# design.net
KiCad netlist of a schematic drawn in Altium Designer
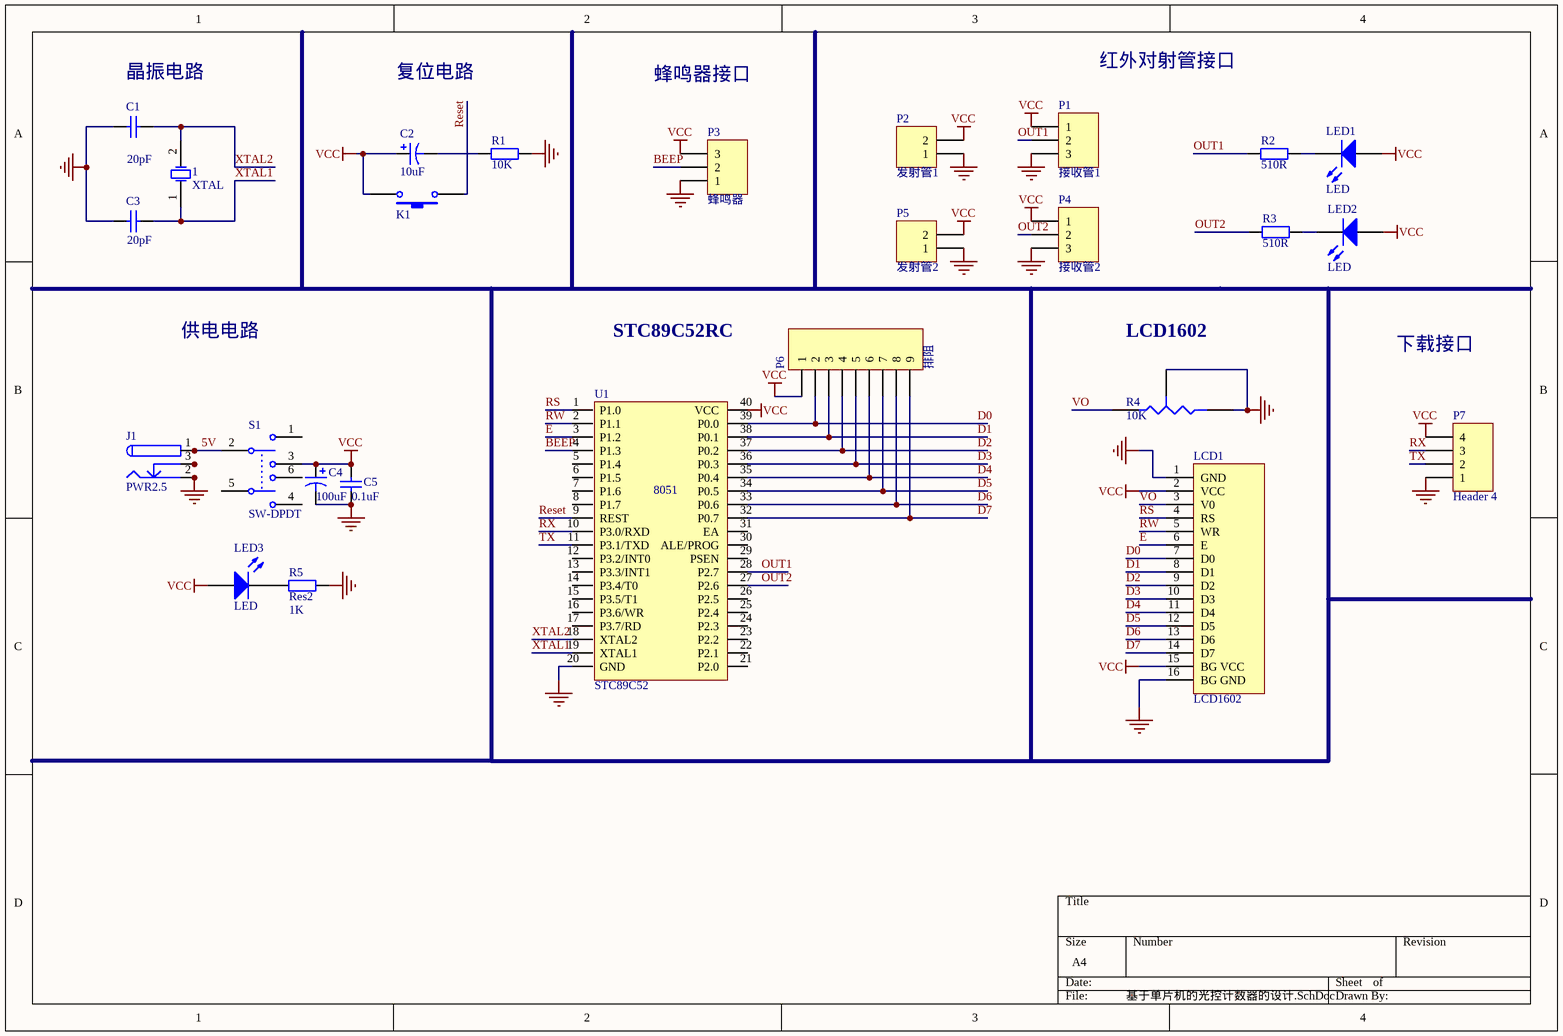
[diagram p0: 基于单片机的光控计数器的设计.SchDoc]

(export (version "E")
  (design (tool "Eeschema 10.0.6"))
  (components
    (comp (ref "1")
      (value "XTAL")
      (footprint "XTAL")
      (description "Crystal Oscillator")
      (fields (field (name "PUBLISHER") "Altium Limited"))
      (libsource (lib "Miscellaneous Devices") (part "XTAL"))
    )
    (comp (ref "C1")
      (value "20pF")
      (footprint "RAD-0.1")
      (description "Capacitor")
      (fields (field (name "Comment") "Cap") (field (name "PUBLISHER") "Altium Limited"))
      (libsource (lib "Miscellaneous Devices") (part "Cap"))
    )
    (comp (ref "C2")
      (value "10uF")
      (footprint "RB.1/.2")
      (description "Polarized Capacitor (Radial)")
      (fields (field (name "Comment") "Cap Pol1") (field (name "PUBLISHER") "Altium Limited"))
      (libsource (lib "Miscellaneous Devices") (part "Cap Pol1"))
    )
    (comp (ref "C3")
      (value "20pF")
      (footprint "RAD-0.1")
      (description "Capacitor")
      (fields (field (name "Comment") "Cap") (field (name "PUBLISHER") "Altium Limited"))
      (libsource (lib "Miscellaneous Devices") (part "Cap"))
    )
    (comp (ref "C4")
      (value "100uF")
      (footprint "RB.1/.2")
      (description "Polarized Capacitor (Radial)")
      (fields (field (name "Comment") "Cap Pol1") (field (name "PUBLISHER") "Altium Limited"))
      (libsource (lib "Miscellaneous Devices") (part "Cap Pol1"))
    )
    (comp (ref "C5")
      (value "0.1uF")
      (footprint "RAD-0.1")
      (description "Capacitor")
      (fields (field (name "Comment") "Cap") (field (name "PUBLISHER") "Altium Limited"))
      (libsource (lib "Miscellaneous Devices") (part "Cap"))
    )
    (comp (ref "J1")
      (value "PWR2.5")
      (footprint "KLD-0202")
      (description "Low Voltage Power Supply Connector")
      (fields (field (name "PUBLISHER") "Altium Limited"))
      (libsource (lib "Miscellaneous Connectors") (part "PWR2.5"))
    )
    (comp (ref "K1") (value "四脚按键") (footprint "四脚按键") (libsource (lib "My library") (part "四脚按键")))
    (comp (ref "LCD1")
      (value "LCD1602")
      (footprint "LCD1602")
      (libsource (lib "My library") (part "LCD1602"))
    )
    (comp (ref "LED1") (value "LED") (footprint "LED") (libsource (lib "My library") (part "LED")))
    (comp (ref "LED2") (value "LED") (footprint "LED") (libsource (lib "My library") (part "LED")))
    (comp (ref "LED3") (value "LED") (footprint "LED") (libsource (lib "My library") (part "LED")))
    (comp (ref "P1")
      (value "接收管1")
      (footprint "HDR1X3")
      (description "Header, 3-Pin")
      (fields (field (name "PUBLISHER") "Altium Limited"))
      (libsource (lib "") (part "Header 3_1"))
    )
    (comp (ref "P2")
      (value "发射管1")
      (footprint "HDR1X2")
      (description "Header, 2-Pin")
      (fields (field (name "PUBLISHER") "Altium Limited"))
      (libsource (lib "Miscellaneous Connectors") (part "Header 2"))
    )
    (comp (ref "P3")
      (value "蜂鸣器")
      (footprint "HDR1X3")
      (description "Header, 3-Pin")
      (fields (field (name "PUBLISHER") "Altium Limited"))
      (libsource (lib "Miscellaneous Connectors") (part "Header 3"))
    )
    (comp (ref "P4")
      (value "接收管2")
      (footprint "HDR1X3")
      (description "Header, 3-Pin")
      (fields (field (name "PUBLISHER") "Altium Limited"))
      (libsource (lib "") (part "Header 3_1"))
    )
    (comp (ref "P5")
      (value "发射管2")
      (footprint "HDR1X2")
      (description "Header, 2-Pin")
      (fields (field (name "PUBLISHER") "Altium Limited"))
      (libsource (lib "Miscellaneous Connectors") (part "Header 2"))
    )
    (comp (ref "P6")
      (value "排阻")
      (footprint "HDR1X9")
      (description "Header, 9-Pin")
      (fields (field (name "PUBLISHER") "Altium Limited"))
      (libsource (lib "Miscellaneous Connectors") (part "Header 9"))
    )
    (comp (ref "P7")
      (value "Header 4")
      (footprint "HDR1X4")
      (description "Header, 4-Pin")
      (fields (field (name "PUBLISHER") "Altium Limited"))
      (libsource (lib "Miscellaneous Connectors") (part "Header 4"))
    )
    (comp (ref "R1")
      (value "10K")
      (footprint "AXIAL-0.4")
      (description "Resistor")
      (fields (field (name "Comment") "Res2") (field (name "PUBLISHER") "Altium Limited"))
      (libsource (lib "Miscellaneous Devices") (part "Res2"))
    )
    (comp (ref "R2")
      (value "510R")
      (footprint "AXIAL-0.4")
      (description "Resistor")
      (fields (field (name "Comment") "Res2") (field (name "PUBLISHER") "Altium Limited"))
      (libsource (lib "") (part "Res2_1"))
    )
    (comp (ref "R3")
      (value "510R")
      (footprint "AXIAL-0.4")
      (description "Resistor")
      (fields (field (name "Comment") "Res2") (field (name "PUBLISHER") "Altium Limited"))
      (libsource (lib "") (part "Res2_1"))
    )
    (comp (ref "R4")
      (value "10K")
      (footprint "电位器")
      (description "Tapped Resistor")
      (fields (field (name "Comment") "Res Tap") (field (name "PUBLISHER") "Altium Limited"))
      (libsource (lib "Miscellaneous Devices") (part "Res Tap"))
    )
    (comp (ref "R5")
      (value "Res2")
      (footprint "AXIAL-0.4")
      (description "Resistor")
      (fields (field (name "ALTIUM_VALUE") "1K") (field (name "PUBLISHER") "Altium Limited"))
      (libsource (lib "") (part "Res2_1"))
    )
    (comp (ref "S1")
      (value "SW-DPDT")
      (footprint "SWITCH_B1")
      (description "单刀双掷开关")
      (fields (field (name "PUBLISHER") "Altium Limited"))
      (libsource (lib "Fszhang") (part "SW-DPDT"))
    )
    (comp (ref "U1") (value "STC89C52") (footprint "DIP-40") (libsource (lib "My library") (part "STC89C51")))
  )
  (nets
    (net (code "1") (name "/5V") (class "Default")
      (node (ref "J1") (pin "1") (pinfunction "1_1") (pintype "power_in"))
      (node (ref "J1") (pin "1A") (pinfunction "1A_1A") (pintype "power_in"))
      (node (ref "J1") (pin "1B") (pinfunction "1B_1B") (pintype "power_in"))
      (node (ref "S1") (pin "2") (pinfunction "2_2") (pintype "passive"))
    )
    (net (code "2") (name "/BEEP") (class "Default")
      (node (ref "P3") (pin "2") (pinfunction "2_2") (pintype "passive"))
      (node (ref "U1") (pin "4") (pinfunction "P1.3_4") (pintype "passive"))
    )
    (net (code "3") (name "/D0") (class "Default")
      (node (ref "LCD1") (pin "7") (pinfunction "D0_7") (pintype "power_in"))
      (node (ref "P6") (pin "2") (pinfunction "2_2") (pintype "passive"))
      (node (ref "U1") (pin "39") (pinfunction "P0.0_39") (pintype "passive"))
    )
    (net (code "4") (name "/D1") (class "Default")
      (node (ref "LCD1") (pin "8") (pinfunction "D1_8") (pintype "power_in"))
      (node (ref "P6") (pin "3") (pinfunction "3_3") (pintype "passive"))
      (node (ref "U1") (pin "38") (pinfunction "P0.1_38") (pintype "passive"))
    )
    (net (code "5") (name "/D2") (class "Default")
      (node (ref "LCD1") (pin "9") (pinfunction "D2_9") (pintype "power_in"))
      (node (ref "P6") (pin "4") (pinfunction "4_4") (pintype "passive"))
      (node (ref "U1") (pin "37") (pinfunction "P0.2_37") (pintype "passive"))
    )
    (net (code "6") (name "/D3") (class "Default")
      (node (ref "LCD1") (pin "10") (pinfunction "D3_10") (pintype "power_in"))
      (node (ref "P6") (pin "5") (pinfunction "5_5") (pintype "passive"))
      (node (ref "U1") (pin "36") (pinfunction "P0.3_36") (pintype "passive"))
    )
    (net (code "7") (name "/D4") (class "Default")
      (node (ref "LCD1") (pin "11") (pinfunction "D4_11") (pintype "power_in"))
      (node (ref "P6") (pin "6") (pinfunction "6_6") (pintype "passive"))
      (node (ref "U1") (pin "35") (pinfunction "P0.4_35") (pintype "passive"))
    )
    (net (code "8") (name "/D5") (class "Default")
      (node (ref "LCD1") (pin "12") (pinfunction "D5_12") (pintype "power_in"))
      (node (ref "P6") (pin "7") (pinfunction "7_7") (pintype "passive"))
      (node (ref "U1") (pin "34") (pinfunction "P0.5_34") (pintype "passive"))
    )
    (net (code "9") (name "/D6") (class "Default")
      (node (ref "LCD1") (pin "13") (pinfunction "D6_13") (pintype "power_in"))
      (node (ref "P6") (pin "8") (pinfunction "8_8") (pintype "passive"))
      (node (ref "U1") (pin "33") (pinfunction "P0.6_33") (pintype "passive"))
    )
    (net (code "10") (name "/D7") (class "Default")
      (node (ref "LCD1") (pin "14") (pinfunction "D7_14") (pintype "power_in"))
      (node (ref "P6") (pin "9") (pinfunction "9_9") (pintype "passive"))
      (node (ref "U1") (pin "32") (pinfunction "P0.7_32") (pintype "passive"))
    )
    (net (code "11") (name "/E") (class "Default")
      (node (ref "LCD1") (pin "6") (pinfunction "E_6") (pintype "power_in"))
      (node (ref "U1") (pin "3") (pinfunction "P1.2_3") (pintype "passive"))
    )
    (net (code "12") (name "/OUT1") (class "Default")
      (node (ref "P1") (pin "2") (pinfunction "2_2") (pintype "passive"))
      (node (ref "R2") (pin "1") (pinfunction "1_1") (pintype "passive"))
      (node (ref "U1") (pin "28") (pinfunction "P2.7_28") (pintype "passive"))
    )
    (net (code "13") (name "/OUT2") (class "Default")
      (node (ref "P4") (pin "2") (pinfunction "2_2") (pintype "passive"))
      (node (ref "R3") (pin "1") (pinfunction "1_1") (pintype "passive"))
      (node (ref "U1") (pin "27") (pinfunction "P2.6_27") (pintype "passive"))
    )
    (net (code "14") (name "/RS") (class "Default")
      (node (ref "LCD1") (pin "4") (pinfunction "RS_4") (pintype "power_in"))
      (node (ref "U1") (pin "1") (pinfunction "P1.0_1") (pintype "passive"))
    )
    (net (code "15") (name "/RW") (class "Default")
      (node (ref "LCD1") (pin "5") (pinfunction "WR_5") (pintype "power_in"))
      (node (ref "U1") (pin "2") (pinfunction "P1.1_2") (pintype "passive"))
    )
    (net (code "16") (name "/RX") (class "Default")
      (node (ref "P7") (pin "3") (pinfunction "3_3") (pintype "passive"))
      (node (ref "U1") (pin "10") (pinfunction "P3.0/RXD_10") (pintype "passive"))
    )
    (net (code "17") (name "/Reset") (class "Default")
      (node (ref "K1") (pin "2") (pinfunction "2_2") (pintype "passive"))
      (node (ref "U1") (pin "9") (pinfunction "REST_9") (pintype "passive"))
    )
    (net (code "18") (name "/TX") (class "Default")
      (node (ref "P7") (pin "2") (pinfunction "2_2") (pintype "passive"))
      (node (ref "U1") (pin "11") (pinfunction "P3.1/TXD_11") (pintype "passive"))
    )
    (net (code "19") (name "/VO") (class "Default")
      (node (ref "LCD1") (pin "3") (pinfunction "V0_3") (pintype "power_in"))
      (node (ref "R4") (pin "1") (pinfunction "A_1") (pintype "passive"))
    )
    (net (code "20") (name "/XTAL1") (class "Default")
      (node (ref "1") (pin "1") (pinfunction "OSC1_1") (pintype "passive"))
      (node (ref "C3") (pin "1") (pinfunction "1_1") (pintype "passive"))
      (node (ref "U1") (pin "19") (pinfunction "XTAL1_19") (pintype "passive"))
    )
    (net (code "21") (name "/XTAL2") (class "Default")
      (node (ref "1") (pin "2") (pinfunction "OSC2_2") (pintype "passive"))
      (node (ref "C1") (pin "1") (pinfunction "1_1") (pintype "passive"))
      (node (ref "U1") (pin "18") (pinfunction "XTAL2_18") (pintype "passive"))
    )
    (net (code "22") (name "GND") (class "Default")
      (node (ref "C1") (pin "2") (pinfunction "2_2") (pintype "passive"))
      (node (ref "C3") (pin "2") (pinfunction "2_2") (pintype "passive"))
      (node (ref "C4") (pin "2") (pinfunction "2_2") (pintype "passive"))
      (node (ref "C5") (pin "1") (pinfunction "1_1") (pintype "passive"))
      (node (ref "J1") (pin "2") (pinfunction "2_2") (pintype "power_in"))
      (node (ref "J1") (pin "2A") (pinfunction "2A_2A") (pintype "power_in"))
      (node (ref "J1") (pin "2B") (pinfunction "2B_2B") (pintype "power_in"))
      (node (ref "LCD1") (pin "1") (pinfunction "GND_1") (pintype "power_in"))
      (node (ref "LCD1") (pin "16") (pinfunction "BG_GND_16") (pintype "power_in"))
      (node (ref "P1") (pin "3") (pinfunction "3_3") (pintype "passive"))
      (node (ref "P2") (pin "1") (pinfunction "1_1") (pintype "passive"))
      (node (ref "P3") (pin "1") (pinfunction "1_1") (pintype "passive"))
      (node (ref "P4") (pin "3") (pinfunction "3_3") (pintype "passive"))
      (node (ref "P5") (pin "1") (pinfunction "1_1") (pintype "passive"))
      (node (ref "P7") (pin "1") (pinfunction "1_1") (pintype "passive"))
      (node (ref "R1") (pin "1") (pinfunction "1_1") (pintype "passive"))
      (node (ref "R4") (pin "2") (pinfunction "B_2") (pintype "passive"))
      (node (ref "R4") (pin "3") (pinfunction "TAP_3") (pintype "passive"))
      (node (ref "R5") (pin "2") (pinfunction "2_2") (pintype "passive"))
      (node (ref "U1") (pin "20") (pinfunction "GND_20") (pintype "passive"))
    )
    (net (code "23") (name "Net-(C2-Pad2)") (class "Default")
      (node (ref "C2") (pin "2") (pinfunction "2_2") (pintype "passive"))
      (node (ref "R1") (pin "2") (pinfunction "2_2") (pintype "passive"))
    )
    (net (code "24") (name "Net-(J1-Pad3)") (class "Default")
      (node (ref "J1") (pin "3") (pinfunction "3_3") (pintype "power_in"))
      (node (ref "J1") (pin "3A") (pinfunction "3A_3A") (pintype "power_in"))
      (node (ref "J1") (pin "3B") (pinfunction "3B_3B") (pintype "power_in"))
    )
    (net (code "25") (name "Net-(LED1-Pad2)") (class "Default")
      (node (ref "LED1") (pin "2") (pinfunction "2_2") (pintype "passive"))
      (node (ref "R2") (pin "2") (pinfunction "2_2") (pintype "passive"))
    )
    (net (code "26") (name "Net-(LED2-Pad2)") (class "Default")
      (node (ref "LED2") (pin "2") (pinfunction "2_2") (pintype "passive"))
      (node (ref "R3") (pin "2") (pinfunction "2_2") (pintype "passive"))
    )
    (net (code "27") (name "Net-(LED3-Pad2)") (class "Default")
      (node (ref "LED3") (pin "2") (pinfunction "2_2") (pintype "passive"))
      (node (ref "R5") (pin "1") (pinfunction "1_1") (pintype "passive"))
    )
    (net (code "28") (name "VCC") (class "Default")
      (node (ref "C2") (pin "1") (pinfunction "1_1") (pintype "passive"))
      (node (ref "C4") (pin "1") (pinfunction "1_1") (pintype "passive"))
      (node (ref "C5") (pin "2") (pinfunction "2_2") (pintype "passive"))
      (node (ref "K1") (pin "1") (pinfunction "1_1") (pintype "passive"))
      (node (ref "LCD1") (pin "15") (pinfunction "BG_VCC_15") (pintype "power_in"))
      (node (ref "LCD1") (pin "2") (pinfunction "VCC_2") (pintype "power_in"))
      (node (ref "LED1") (pin "1") (pinfunction "1_1") (pintype "passive"))
      (node (ref "LED2") (pin "1") (pinfunction "1_1") (pintype "passive"))
      (node (ref "LED3") (pin "1") (pinfunction "1_1") (pintype "passive"))
      (node (ref "P1") (pin "1") (pinfunction "1_1") (pintype "passive"))
      (node (ref "P2") (pin "2") (pinfunction "2_2") (pintype "passive"))
      (node (ref "P3") (pin "3") (pinfunction "3_3") (pintype "passive"))
      (node (ref "P4") (pin "1") (pinfunction "1_1") (pintype "passive"))
      (node (ref "P5") (pin "2") (pinfunction "2_2") (pintype "passive"))
      (node (ref "P6") (pin "1") (pinfunction "1_1") (pintype "passive"))
      (node (ref "P7") (pin "4") (pinfunction "4_4") (pintype "passive"))
      (node (ref "S1") (pin "3") (pinfunction "3_3") (pintype "passive"))
      (node (ref "U1") (pin "40") (pinfunction "VCC_40") (pintype "passive"))
    )
    (net (code "29") (name "unconnected-(S1-Pad1)") (class "Default")
      (node (ref "S1") (pin "1") (pinfunction "1_1") (pintype "passive"))
    )
    (net (code "30") (name "unconnected-(S1-Pad4)") (class "Default")
      (node (ref "S1") (pin "4") (pinfunction "4_4") (pintype "passive"))
    )
    (net (code "31") (name "unconnected-(S1-Pad5)") (class "Default")
      (node (ref "S1") (pin "5") (pinfunction "5_5") (pintype "passive"))
    )
    (net (code "32") (name "unconnected-(S1-Pad6)") (class "Default")
      (node (ref "S1") (pin "6") (pinfunction "6_6") (pintype "passive"))
    )
    (net (code "33") (name "unconnected-(U1-ALE{slash}PROG-Pad30)") (class "Default")
      (node (ref "U1") (pin "30") (pinfunction "ALE/PROG_30") (pintype "passive"))
    )
    (net (code "34") (name "unconnected-(U1-EA-Pad31)") (class "Default")
      (node (ref "U1") (pin "31") (pinfunction "EA_31") (pintype "passive"))
    )
    (net (code "35") (name "unconnected-(U1-P1.4-Pad5)") (class "Default")
      (node (ref "U1") (pin "5") (pinfunction "P1.4_5") (pintype "passive"))
    )
    (net (code "36") (name "unconnected-(U1-P1.5-Pad6)") (class "Default")
      (node (ref "U1") (pin "6") (pinfunction "P1.5_6") (pintype "passive"))
    )
    (net (code "37") (name "unconnected-(U1-P1.6-Pad7)") (class "Default")
      (node (ref "U1") (pin "7") (pinfunction "P1.6_7") (pintype "passive"))
    )
    (net (code "38") (name "unconnected-(U1-P1.7-Pad8)") (class "Default")
      (node (ref "U1") (pin "8") (pinfunction "P1.7_8") (pintype "passive"))
    )
    (net (code "39") (name "unconnected-(U1-P2.0-Pad21)") (class "Default")
      (node (ref "U1") (pin "21") (pinfunction "P2.0_21") (pintype "passive"))
    )
    (net (code "40") (name "unconnected-(U1-P2.1-Pad22)") (class "Default")
      (node (ref "U1") (pin "22") (pinfunction "P2.1_22") (pintype "passive"))
    )
    (net (code "41") (name "unconnected-(U1-P2.2-Pad23)") (class "Default")
      (node (ref "U1") (pin "23") (pinfunction "P2.2_23") (pintype "passive"))
    )
    (net (code "42") (name "unconnected-(U1-P2.3-Pad24)") (class "Default")
      (node (ref "U1") (pin "24") (pinfunction "P2.3_24") (pintype "passive"))
    )
    (net (code "43") (name "unconnected-(U1-P2.4-Pad25)") (class "Default")
      (node (ref "U1") (pin "25") (pinfunction "P2.4_25") (pintype "passive"))
    )
    (net (code "44") (name "unconnected-(U1-P2.5-Pad26)") (class "Default")
      (node (ref "U1") (pin "26") (pinfunction "P2.5_26") (pintype "passive"))
    )
    (net (code "45") (name "unconnected-(U1-P3.2{slash}INT0-Pad12)") (class "Default")
      (node (ref "U1") (pin "12") (pinfunction "P3.2/INT0_12") (pintype "passive"))
    )
    (net (code "46") (name "unconnected-(U1-P3.3{slash}INT1-Pad13)") (class "Default")
      (node (ref "U1") (pin "13") (pinfunction "P3.3/INT1_13") (pintype "passive"))
    )
    (net (code "47") (name "unconnected-(U1-P3.4{slash}T0-Pad14)") (class "Default")
      (node (ref "U1") (pin "14") (pinfunction "P3.4/T0_14") (pintype "passive"))
    )
    (net (code "48") (name "unconnected-(U1-P3.5{slash}T1-Pad15)") (class "Default")
      (node (ref "U1") (pin "15") (pinfunction "P3.5/T1_15") (pintype "passive"))
    )
    (net (code "49") (name "unconnected-(U1-P3.6{slash}WR-Pad16)") (class "Default")
      (node (ref "U1") (pin "16") (pinfunction "P3.6/WR_16") (pintype "passive"))
    )
    (net (code "50") (name "unconnected-(U1-P3.7{slash}RD-Pad17)") (class "Default")
      (node (ref "U1") (pin "17") (pinfunction "P3.7/RD_17") (pintype "passive"))
    )
    (net (code "51") (name "unconnected-(U1-PSEN-Pad29)") (class "Default")
      (node (ref "U1") (pin "29") (pinfunction "PSEN_29") (pintype "passive"))
    )
  )
)
